# Wemos-ESP32_MAX7219_v1.net
KiCad netlist of a schematic drawn in EAGLE
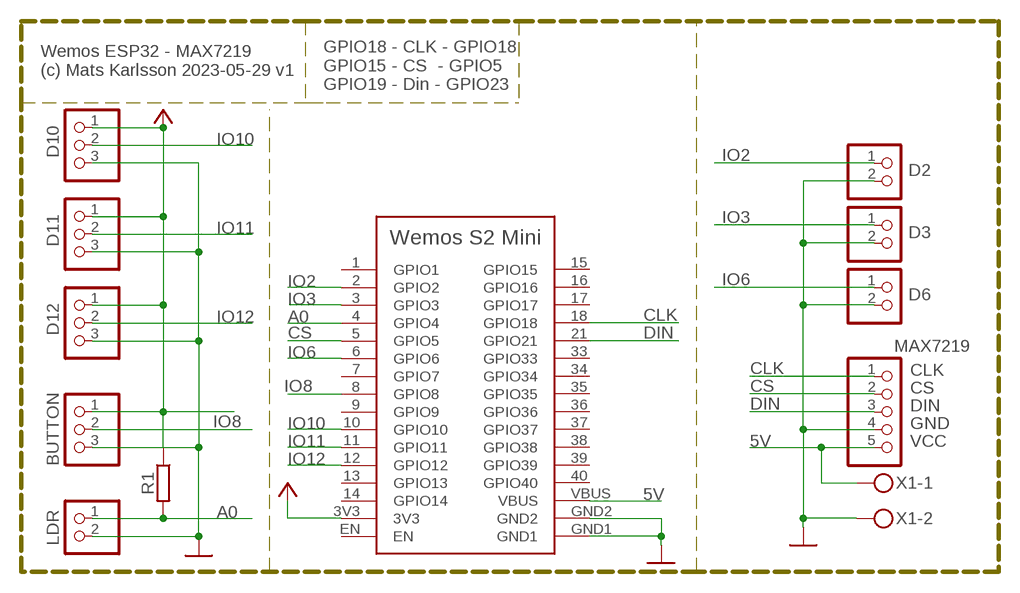
[diagram p0: schematic, sheet 1]

(export (version "E")
  (design (tool "Eeschema 10.0.6"))
  (components
    (comp (ref "BUTTON")
      (value "PINHD-1X3")
      (footprint "eagle-import:1X03")
      (libsource (lib "eagle-import") (part "PINHD-1X3"))
    )
    (comp (ref "D2")
      (value "PINHD-1X2")
      (footprint "eagle-import:1X02")
      (libsource (lib "eagle-import") (part "PINHD-1X2"))
    )
    (comp (ref "D3")
      (value "PINHD-1X2")
      (footprint "eagle-import:1X02")
      (libsource (lib "eagle-import") (part "PINHD-1X2"))
    )
    (comp (ref "D6")
      (value "PINHD-1X2")
      (footprint "eagle-import:1X02")
      (libsource (lib "eagle-import") (part "PINHD-1X2"))
    )
    (comp (ref "D10")
      (value "PINHD-1X3")
      (footprint "eagle-import:1X03")
      (libsource (lib "eagle-import") (part "PINHD-1X3"))
    )
    (comp (ref "D11")
      (value "PINHD-1X3")
      (footprint "eagle-import:1X03")
      (libsource (lib "eagle-import") (part "PINHD-1X3"))
    )
    (comp (ref "D12")
      (value "PINHD-1X3")
      (footprint "eagle-import:1X03")
      (libsource (lib "eagle-import") (part "PINHD-1X3"))
    )
    (comp (ref "LDR")
      (value "PINHD-1X2")
      (footprint "eagle-import:1X02")
      (libsource (lib "eagle-import") (part "PINHD-1X2"))
    )
    (comp (ref "MAX7219")
      (value "PINHD-1X5")
      (footprint "eagle-import:1X05")
      (libsource (lib "eagle-import") (part "PINHD-1X5"))
    )
    (comp (ref "R1")
      (value "R-EU_M0805")
      (footprint "eagle-import:M0805")
      (libsource (lib "eagle-import") (part "R-EU_M0805"))
    )
    (comp (ref "U$1")
      (value "WEMOS_S2_MINI")
      (footprint "eagle-import:WEMOS_S2_MINI")
      (libsource (lib "eagle-import") (part "WEMOS_S2_MINI"))
    )
    (comp (ref "X1")
      (value "W237-102")
      (footprint "eagle-import:W237-102")
      (fields (field (name "MPN") "237-102"))
      (libsource (lib "eagle-import") (part "W237-102"))
    )
  )
  (nets
    (net (code "1") (name "/5V") (class "Default")
      (node (ref "MAX7219") (pin "5") (pinfunction "5_5") (pintype "passive"))
      (node (ref "U$1") (pin "VBUS") (pinfunction "VBUS_VBUS") (pintype "power_in"))
      (node (ref "X1") (pin "1") (pinfunction "KL_1") (pintype "passive"))
    )
    (net (code "2") (name "/A0") (class "Default")
      (node (ref "LDR") (pin "1") (pinfunction "1_1") (pintype "passive"))
      (node (ref "R1") (pin "2") (pinfunction "2_2") (pintype "passive"))
      (node (ref "U$1") (pin "4") (pinfunction "GPIO4_4") (pintype "bidirectional"))
    )
    (net (code "3") (name "/CLK") (class "Default")
      (node (ref "MAX7219") (pin "1") (pinfunction "1_1") (pintype "passive"))
      (node (ref "U$1") (pin "18") (pinfunction "GPIO18_18") (pintype "bidirectional"))
    )
    (net (code "4") (name "/CS") (class "Default")
      (node (ref "MAX7219") (pin "2") (pinfunction "2_2") (pintype "passive"))
      (node (ref "U$1") (pin "5") (pinfunction "GPIO5_5") (pintype "bidirectional"))
    )
    (net (code "5") (name "/DIN") (class "Default")
      (node (ref "MAX7219") (pin "3") (pinfunction "3_3") (pintype "passive"))
      (node (ref "U$1") (pin "21") (pinfunction "GPIO21_21") (pintype "bidirectional"))
    )
    (net (code "6") (name "/IO2") (class "Default")
      (node (ref "D2") (pin "1") (pinfunction "1_1") (pintype "passive"))
      (node (ref "U$1") (pin "2") (pinfunction "GPIO2_2") (pintype "bidirectional"))
    )
    (net (code "7") (name "/IO3") (class "Default")
      (node (ref "D3") (pin "1") (pinfunction "1_1") (pintype "passive"))
      (node (ref "U$1") (pin "3") (pinfunction "GPIO3_3") (pintype "bidirectional"))
    )
    (net (code "8") (name "/IO6") (class "Default")
      (node (ref "D6") (pin "1") (pinfunction "1_1") (pintype "passive"))
      (node (ref "U$1") (pin "6") (pinfunction "GPIO6_6") (pintype "bidirectional"))
    )
    (net (code "9") (name "/IO8") (class "Default")
      (node (ref "BUTTON") (pin "2") (pinfunction "2_2") (pintype "passive"))
      (node (ref "U$1") (pin "8") (pinfunction "GPIO8_8") (pintype "bidirectional"))
    )
    (net (code "10") (name "/IO10") (class "Default")
      (node (ref "D10") (pin "2") (pinfunction "2_2") (pintype "passive"))
      (node (ref "U$1") (pin "10") (pinfunction "GPIO10_10") (pintype "bidirectional"))
    )
    (net (code "11") (name "/IO11") (class "Default")
      (node (ref "D11") (pin "2") (pinfunction "2_2") (pintype "passive"))
      (node (ref "U$1") (pin "11") (pinfunction "GPIO11_11") (pintype "bidirectional"))
    )
    (net (code "12") (name "/IO12") (class "Default")
      (node (ref "D12") (pin "2") (pinfunction "2_2") (pintype "passive"))
      (node (ref "U$1") (pin "12") (pinfunction "GPIO12_12") (pintype "bidirectional"))
    )
    (net (code "13") (name "GND") (class "Default")
      (node (ref "BUTTON") (pin "3") (pinfunction "3_3") (pintype "passive"))
      (node (ref "D10") (pin "3") (pinfunction "3_3") (pintype "passive"))
      (node (ref "D11") (pin "3") (pinfunction "3_3") (pintype "passive"))
      (node (ref "D12") (pin "3") (pinfunction "3_3") (pintype "passive"))
      (node (ref "D2") (pin "2") (pinfunction "2_2") (pintype "passive"))
      (node (ref "D3") (pin "2") (pinfunction "2_2") (pintype "passive"))
      (node (ref "D6") (pin "2") (pinfunction "2_2") (pintype "passive"))
      (node (ref "LDR") (pin "2") (pinfunction "2_2") (pintype "passive"))
      (node (ref "MAX7219") (pin "4") (pinfunction "4_4") (pintype "passive"))
      (node (ref "U$1") (pin "GND1") (pinfunction "GND1_GND1") (pintype "power_in"))
      (node (ref "U$1") (pin "GND2") (pinfunction "GND2_GND2") (pintype "power_in"))
      (node (ref "X1") (pin "2") (pinfunction "KL_2") (pintype "passive"))
    )
    (net (code "14") (name "VCC") (class "Default")
      (node (ref "BUTTON") (pin "1") (pinfunction "1_1") (pintype "passive"))
      (node (ref "D10") (pin "1") (pinfunction "1_1") (pintype "passive"))
      (node (ref "D11") (pin "1") (pinfunction "1_1") (pintype "passive"))
      (node (ref "D12") (pin "1") (pinfunction "1_1") (pintype "passive"))
      (node (ref "R1") (pin "1") (pinfunction "1_1") (pintype "passive"))
      (node (ref "U$1") (pin "3V3") (pinfunction "3V3_3V3") (pintype "power_in"))
    )
    (net (code "15") (name "unconnected-(U$1-GPIO1-Pad1)") (class "Default")
      (node (ref "U$1") (pin "1") (pinfunction "GPIO1_1") (pintype "bidirectional"))
    )
    (net (code "16") (name "unconnected-(U$1-GPIO7-Pad7)") (class "Default")
      (node (ref "U$1") (pin "7") (pinfunction "GPIO7_7") (pintype "bidirectional"))
    )
    (net (code "17") (name "unconnected-(U$1-GPIO9-Pad9)") (class "Default")
      (node (ref "U$1") (pin "9") (pinfunction "GPIO9_9") (pintype "bidirectional"))
    )
    (net (code "18") (name "unconnected-(U$1-GPIO13-Pad13)") (class "Default")
      (node (ref "U$1") (pin "13") (pinfunction "GPIO13_13") (pintype "bidirectional"))
    )
    (net (code "19") (name "unconnected-(U$1-GPIO14-Pad14)") (class "Default")
      (node (ref "U$1") (pin "14") (pinfunction "GPIO14_14") (pintype "bidirectional"))
    )
    (net (code "20") (name "unconnected-(U$1-GPIO15-Pad15)") (class "Default")
      (node (ref "U$1") (pin "15") (pinfunction "GPIO15_15") (pintype "bidirectional"))
    )
    (net (code "21") (name "unconnected-(U$1-GPIO16-Pad16)") (class "Default")
      (node (ref "U$1") (pin "16") (pinfunction "GPIO16_16") (pintype "bidirectional"))
    )
    (net (code "22") (name "unconnected-(U$1-GPIO17-Pad17)") (class "Default")
      (node (ref "U$1") (pin "17") (pinfunction "GPIO17_17") (pintype "bidirectional"))
    )
    (net (code "23") (name "unconnected-(U$1-GPIO33-Pad33)") (class "Default")
      (node (ref "U$1") (pin "33") (pinfunction "GPIO33_33") (pintype "bidirectional"))
    )
    (net (code "24") (name "unconnected-(U$1-GPIO34-Pad34)") (class "Default")
      (node (ref "U$1") (pin "34") (pinfunction "GPIO34_34") (pintype "bidirectional"))
    )
    (net (code "25") (name "unconnected-(U$1-GPIO35-Pad35)") (class "Default")
      (node (ref "U$1") (pin "35") (pinfunction "GPIO35_35") (pintype "bidirectional"))
    )
    (net (code "26") (name "unconnected-(U$1-GPIO36-Pad36)") (class "Default")
      (node (ref "U$1") (pin "36") (pinfunction "GPIO36_36") (pintype "bidirectional"))
    )
    (net (code "27") (name "unconnected-(U$1-GPIO37-Pad37)") (class "Default")
      (node (ref "U$1") (pin "37") (pinfunction "GPIO37_37") (pintype "bidirectional"))
    )
    (net (code "28") (name "unconnected-(U$1-GPIO38-Pad38)") (class "Default")
      (node (ref "U$1") (pin "38") (pinfunction "GPIO38_38") (pintype "bidirectional"))
    )
    (net (code "29") (name "unconnected-(U$1-GPIO39-Pad39)") (class "Default")
      (node (ref "U$1") (pin "39") (pinfunction "GPIO39_39") (pintype "bidirectional"))
    )
    (net (code "30") (name "unconnected-(U$1-GPIO40-Pad40)") (class "Default")
      (node (ref "U$1") (pin "40") (pinfunction "GPIO40_40") (pintype "bidirectional"))
    )
    (net (code "31") (name "unconnected-(U$1-PadEN)") (class "Default")
      (node (ref "U$1") (pin "EN") (pinfunction "EN_EN") (pintype "input"))
    )
  )
)
